# shield.net
KiCad netlist of a schematic drawn in EAGLE
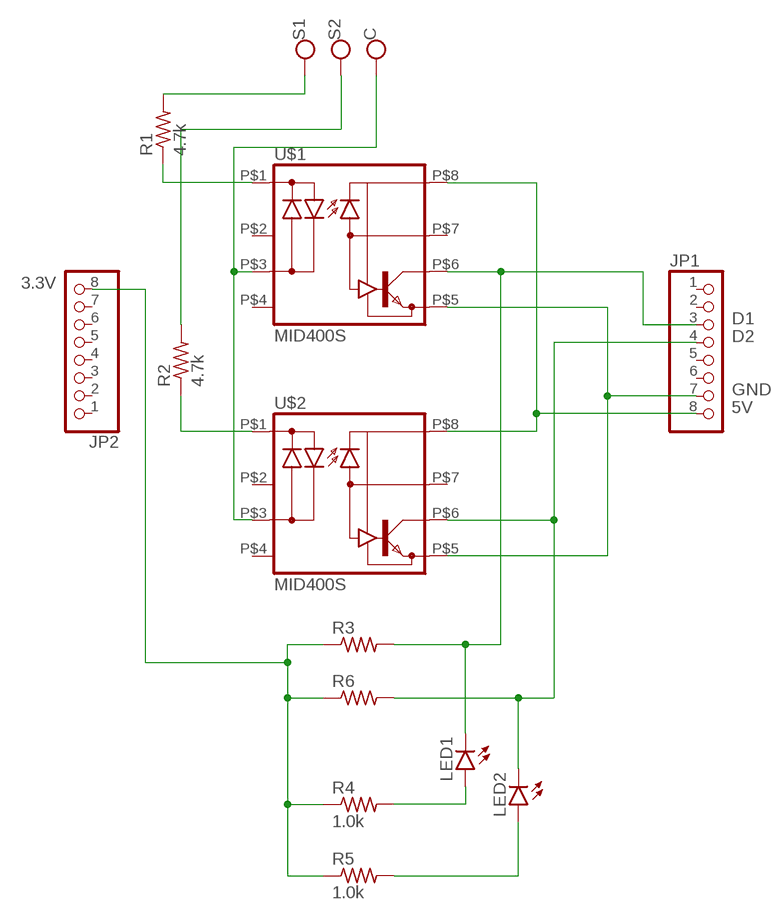
[diagram p0: schematic, sheet 1]

(export (version "E")
  (design (tool "Eeschema 10.0.6"))
  (components
    (comp (ref "JP1")
      (value "PINHD-1X8/OCT")
      (footprint "eagle-import:1X08_OCT")
      (libsource (lib "eagle-import") (part "PINHD-1X8/OCT"))
    )
    (comp (ref "JP2")
      (value "PINHD-1X8/OCT")
      (footprint "eagle-import:1X08_OCT")
      (libsource (lib "eagle-import") (part "PINHD-1X8/OCT"))
    )
    (comp (ref "LED1")
      (value "LEDSML0603")
      (footprint "eagle-import:SML0603")
      (libsource (lib "eagle-import") (part "LEDSML0603"))
    )
    (comp (ref "LED2")
      (value "LEDSML0603")
      (footprint "eagle-import:SML0603")
      (libsource (lib "eagle-import") (part "LEDSML0603"))
    )
    (comp (ref "R1")
      (value "4.7k")
      (footprint "eagle-import:R0603")
      (libsource (lib "eagle-import") (part "R-US_R0603"))
    )
    (comp (ref "R2")
      (value "4.7k")
      (footprint "eagle-import:R0603")
      (libsource (lib "eagle-import") (part "R-US_R0603"))
    )
    (comp (ref "R3")
      (value "R-US_R0603")
      (footprint "eagle-import:R0603")
      (libsource (lib "eagle-import") (part "R-US_R0603"))
    )
    (comp (ref "R4")
      (value "1.0k")
      (footprint "eagle-import:R0603")
      (libsource (lib "eagle-import") (part "R-US_R0603"))
    )
    (comp (ref "R5")
      (value "1.0k")
      (footprint "eagle-import:R0603")
      (libsource (lib "eagle-import") (part "R-US_R0603"))
    )
    (comp (ref "R6")
      (value "R-US_R0603")
      (footprint "eagle-import:R0603")
      (libsource (lib "eagle-import") (part "R-US_R0603"))
    )
    (comp (ref "U$1")
      (value "MID400S")
      (footprint "eagle-import:SMT8")
      (libsource (lib "eagle-import") (part "MID400S"))
    )
    (comp (ref "U$2")
      (value "MID400S")
      (footprint "eagle-import:SMT8")
      (libsource (lib "eagle-import") (part "MID400S"))
    )
    (comp (ref "X1")
      (value "AK550/3QUIET")
      (footprint "eagle-import:AK550_3-N")
      (libsource (lib "eagle-import") (part "AK550/3QUIET"))
    )
  )
  (nets
    (net (code "1") (name "/3.3V") (class "Default")
      (node (ref "JP2") (pin "8") (pinfunction "8_8") (pintype "passive"))
      (node (ref "R3") (pin "1") (pinfunction "1_1") (pintype "passive"))
      (node (ref "R4") (pin "1") (pinfunction "1_1") (pintype "passive"))
      (node (ref "R5") (pin "1") (pinfunction "1_1") (pintype "passive"))
      (node (ref "R6") (pin "1") (pinfunction "1_1") (pintype "passive"))
    )
    (net (code "2") (name "/5V") (class "Default")
      (node (ref "JP1") (pin "8") (pinfunction "8_8") (pintype "passive"))
      (node (ref "U$1") (pin "P$8") (pinfunction "VCC_P$8") (pintype "passive"))
      (node (ref "U$2") (pin "P$8") (pinfunction "VCC_P$8") (pintype "passive"))
    )
    (net (code "3") (name "/C") (class "Default")
      (node (ref "U$1") (pin "P$3") (pinfunction "AC2_P$3") (pintype "passive"))
      (node (ref "U$2") (pin "P$3") (pinfunction "AC2_P$3") (pintype "passive"))
      (node (ref "X1") (pin "1") (pinfunction "KL_1") (pintype "passive"))
    )
    (net (code "4") (name "/D1") (class "Default")
      (node (ref "JP1") (pin "3") (pinfunction "3_3") (pintype "passive"))
      (node (ref "LED1") (pin "C") (pinfunction "C_C") (pintype "passive"))
      (node (ref "R3") (pin "2") (pinfunction "2_2") (pintype "passive"))
      (node (ref "U$1") (pin "P$6") (pinfunction "VO_P$6") (pintype "passive"))
    )
    (net (code "5") (name "/D2") (class "Default")
      (node (ref "JP1") (pin "4") (pinfunction "4_4") (pintype "passive"))
      (node (ref "LED2") (pin "C") (pinfunction "C_C") (pintype "passive"))
      (node (ref "R6") (pin "2") (pinfunction "2_2") (pintype "passive"))
      (node (ref "U$2") (pin "P$6") (pinfunction "VO_P$6") (pintype "passive"))
    )
    (net (code "6") (name "/GND") (class "Default")
      (node (ref "JP1") (pin "7") (pinfunction "7_7") (pintype "passive"))
      (node (ref "U$1") (pin "P$5") (pinfunction "GND_P$5") (pintype "passive"))
      (node (ref "U$2") (pin "P$5") (pinfunction "GND_P$5") (pintype "passive"))
    )
    (net (code "7") (name "/S1") (class "Default")
      (node (ref "R1") (pin "2") (pinfunction "2_2") (pintype "passive"))
      (node (ref "X1") (pin "3") (pinfunction "KL_3") (pintype "passive"))
    )
    (net (code "8") (name "/S2") (class "Default")
      (node (ref "R2") (pin "2") (pinfunction "2_2") (pintype "passive"))
      (node (ref "X1") (pin "2") (pinfunction "KL_2") (pintype "passive"))
    )
    (net (code "9") (name "Net-(LED1-PadA)") (class "Default")
      (node (ref "LED1") (pin "A") (pinfunction "A_A") (pintype "passive"))
      (node (ref "R4") (pin "2") (pinfunction "2_2") (pintype "passive"))
    )
    (net (code "10") (name "Net-(LED2-PadA)") (class "Default")
      (node (ref "LED2") (pin "A") (pinfunction "A_A") (pintype "passive"))
      (node (ref "R5") (pin "2") (pinfunction "2_2") (pintype "passive"))
    )
    (net (code "11") (name "Net-(U$1-AC1)") (class "Default")
      (node (ref "R1") (pin "1") (pinfunction "1_1") (pintype "passive"))
      (node (ref "U$1") (pin "P$1") (pinfunction "AC1_P$1") (pintype "passive"))
    )
    (net (code "12") (name "Net-(U$2-AC1)") (class "Default")
      (node (ref "R2") (pin "1") (pinfunction "1_1") (pintype "passive"))
      (node (ref "U$2") (pin "P$1") (pinfunction "AC1_P$1") (pintype "passive"))
    )
    (net (code "13") (name "unconnected-(JP1-Pad1)") (class "Default")
      (node (ref "JP1") (pin "1") (pinfunction "1_1") (pintype "passive"))
    )
    (net (code "14") (name "unconnected-(JP1-Pad2)") (class "Default")
      (node (ref "JP1") (pin "2") (pinfunction "2_2") (pintype "passive"))
    )
    (net (code "15") (name "unconnected-(JP1-Pad5)") (class "Default")
      (node (ref "JP1") (pin "5") (pinfunction "5_5") (pintype "passive"))
    )
    (net (code "16") (name "unconnected-(JP1-Pad6)") (class "Default")
      (node (ref "JP1") (pin "6") (pinfunction "6_6") (pintype "passive"))
    )
    (net (code "17") (name "unconnected-(JP2-Pad1)") (class "Default")
      (node (ref "JP2") (pin "1") (pinfunction "1_1") (pintype "passive"))
    )
    (net (code "18") (name "unconnected-(JP2-Pad2)") (class "Default")
      (node (ref "JP2") (pin "2") (pinfunction "2_2") (pintype "passive"))
    )
    (net (code "19") (name "unconnected-(JP2-Pad3)") (class "Default")
      (node (ref "JP2") (pin "3") (pinfunction "3_3") (pintype "passive"))
    )
    (net (code "20") (name "unconnected-(JP2-Pad4)") (class "Default")
      (node (ref "JP2") (pin "4") (pinfunction "4_4") (pintype "passive"))
    )
    (net (code "21") (name "unconnected-(JP2-Pad5)") (class "Default")
      (node (ref "JP2") (pin "5") (pinfunction "5_5") (pintype "passive"))
    )
    (net (code "22") (name "unconnected-(JP2-Pad6)") (class "Default")
      (node (ref "JP2") (pin "6") (pinfunction "6_6") (pintype "passive"))
    )
    (net (code "23") (name "unconnected-(JP2-Pad7)") (class "Default")
      (node (ref "JP2") (pin "7") (pinfunction "7_7") (pintype "passive"))
    )
    (net (code "24") (name "unconnected-(U$1-AUX-PadP$7)") (class "Default")
      (node (ref "U$1") (pin "P$7") (pinfunction "AUX_P$7") (pintype "passive"))
    )
    (net (code "25") (name "unconnected-(U$1-NC1-PadP$2)") (class "Default")
      (node (ref "U$1") (pin "P$2") (pinfunction "NC1_P$2") (pintype "no_connect"))
    )
    (net (code "26") (name "unconnected-(U$1-NC2-PadP$4)") (class "Default")
      (node (ref "U$1") (pin "P$4") (pinfunction "NC2_P$4") (pintype "no_connect"))
    )
    (net (code "27") (name "unconnected-(U$2-AUX-PadP$7)") (class "Default")
      (node (ref "U$2") (pin "P$7") (pinfunction "AUX_P$7") (pintype "passive"))
    )
    (net (code "28") (name "unconnected-(U$2-NC1-PadP$2)") (class "Default")
      (node (ref "U$2") (pin "P$2") (pinfunction "NC1_P$2") (pintype "no_connect"))
    )
    (net (code "29") (name "unconnected-(U$2-NC2-PadP$4)") (class "Default")
      (node (ref "U$2") (pin "P$4") (pinfunction "NC2_P$4") (pintype "no_connect"))
    )
  )
)
